# design.net
KiCad netlist of a schematic drawn in Altium Designer
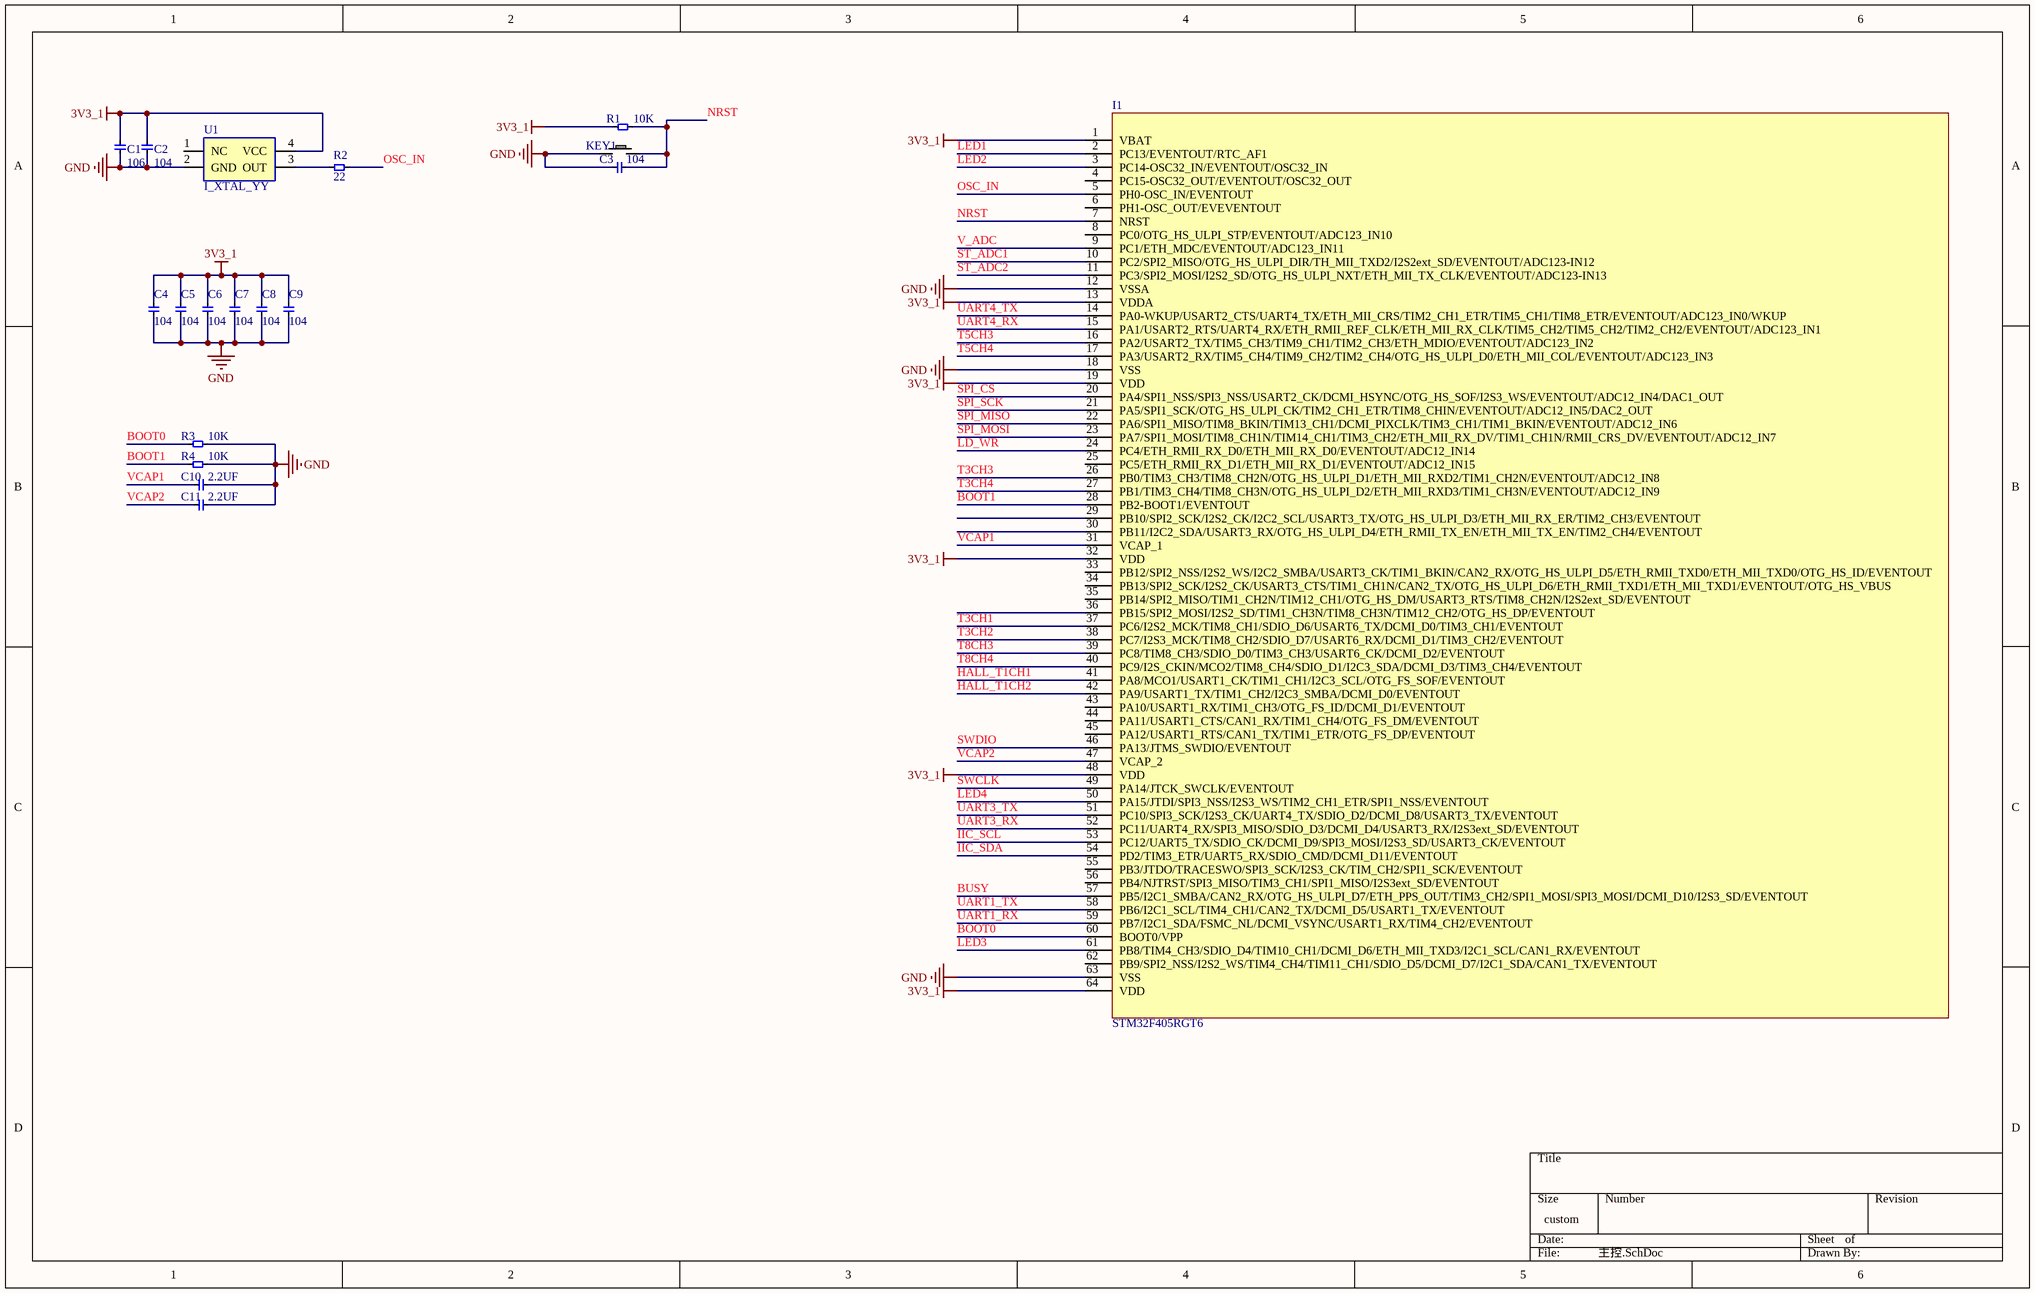
[diagram p0: 主控.SchDoc]

(export (version "E")
  (design (tool "Eeschema 10.0.6"))
  (components
    (comp (ref "C1")
      (value "106")
      (footprint "C_0603")
      (description "无极性贴片电容")
      (libsource (lib "电阻电容电感库") (part "C_无极贴片"))
    )
    (comp (ref "C2")
      (value "104")
      (footprint "C_0603")
      (description "无极性贴片电容")
      (libsource (lib "电阻电容电感库") (part "C_无极贴片"))
    )
    (comp (ref "C3")
      (value "104")
      (footprint "C_0603")
      (description "无极性贴片电容")
      (libsource (lib "电阻电容电感库") (part "C_无极贴片"))
    )
    (comp (ref "C4")
      (value "104")
      (footprint "C_0603")
      (description "无极性贴片电容")
      (libsource (lib "电阻电容电感库") (part "C_无极贴片"))
    )
    (comp (ref "C5")
      (value "104")
      (footprint "C_0603")
      (description "无极性贴片电容")
      (libsource (lib "电阻电容电感库") (part "C_无极贴片"))
    )
    (comp (ref "C6")
      (value "104")
      (footprint "C_0603")
      (description "无极性贴片电容")
      (libsource (lib "电阻电容电感库") (part "C_无极贴片"))
    )
    (comp (ref "C7")
      (value "104")
      (footprint "C_0603")
      (description "无极性贴片电容")
      (libsource (lib "电阻电容电感库") (part "C_无极贴片"))
    )
    (comp (ref "C8")
      (value "104")
      (footprint "C_0603")
      (description "无极性贴片电容")
      (libsource (lib "电阻电容电感库") (part "C_无极贴片"))
    )
    (comp (ref "C9")
      (value "104")
      (footprint "C_0603")
      (description "无极性贴片电容")
      (libsource (lib "电阻电容电感库") (part "C_无极贴片"))
    )
    (comp (ref "C10")
      (value "2.2UF")
      (footprint "C_0603")
      (description "无极性贴片电容")
      (libsource (lib "电阻电容电感库") (part "C_无极贴片"))
    )
    (comp (ref "C11")
      (value "2.2UF")
      (footprint "C_0603")
      (description "无极性贴片电容")
      (libsource (lib "电阻电容电感库") (part "C_无极贴片"))
    )
    (comp (ref "I1")
      (value "STM32F405RGT6")
      (footprint "I_LQFP-64")
      (description "LQFP-64")
      (libsource (lib "集成器件") (part "I_STM32F405RGT6"))
    )
    (comp (ref "KEY1") (value "KEY") (footprint "按键_小四脚") (libsource (lib "王建勇") (part "按键")))
    (comp (ref "R1")
      (value "10K")
      (footprint "R_0603")
      (description "贴片电阻")
      (libsource (lib "电阻电容电感库") (part "R_贴片"))
    )
    (comp (ref "R2")
      (value "22")
      (footprint "R_0603")
      (description "贴片电阻")
      (libsource (lib "电阻电容电感库") (part "R_贴片"))
    )
    (comp (ref "R3")
      (value "10K")
      (footprint "R_0603")
      (description "贴片电阻")
      (libsource (lib "电阻电容电感库") (part "R_贴片"))
    )
    (comp (ref "R4")
      (value "10K")
      (footprint "R_0603")
      (description "贴片电阻")
      (libsource (lib "电阻电容电感库") (part "R_贴片"))
    )
    (comp (ref "U1")
      (value "I_XTAL_YY")
      (footprint "I_XTAL_YYSMD_3.2X2.5")
      (description "有源晶振")
      (libsource (lib "集成器件") (part "I_XTAL_YY"))
    )
  )
  (nets
    (net (code "1") (name "/BOOT0") (class "Default")
      (node (ref "I1") (pin "60") (pinfunction "BOOT0/VPP_60") (pintype "power_in"))
      (node (ref "R3") (pin "1") (pintype "passive"))
    )
    (net (code "2") (name "/BOOT1") (class "Default")
      (node (ref "I1") (pin "28") (pinfunction "PB2-BOOT1/EVENTOUT_28") (pintype "power_in"))
      (node (ref "R4") (pin "1") (pintype "passive"))
    )
    (net (code "3") (name "/BUSY") (class "Default")
      (node (ref "I1") (pin "57") (pinfunction "PB5/I2C1_SMBA/CAN2_RX/OTG_HS_ULPI_D7/ETH_PPS_OUT/TIM3_CH2/SPI1_MOSI/SPI3_MOSI/DCMI_D10/I2S3_SD/EVENTOUT_57") (pintype "power_in"))
    )
    (net (code "4") (name "/HALL_T1CH1") (class "Default")
      (node (ref "I1") (pin "41") (pinfunction "PA8/MCO1/USART1_CK/TIM1_CH1/I2C3_SCL/OTG_FS_SOF/EVENTOUT_41") (pintype "power_in"))
    )
    (net (code "5") (name "/HALL_T1CH2") (class "Default")
      (node (ref "I1") (pin "42") (pinfunction "PA9/USART1_TX/TIM1_CH2/I2C3_SMBA/DCMI_D0/EVENTOUT_42") (pintype "power_in"))
    )
    (net (code "6") (name "/IIC_SCL") (class "Default")
      (node (ref "I1") (pin "53") (pinfunction "PC12/UART5_TX/SDIO_CK/DCMI_D9/SPI3_MOSI/I2S3_SD/USART3_CK/EVENTOUT_53") (pintype "power_in"))
    )
    (net (code "7") (name "/IIC_SDA") (class "Default")
      (node (ref "I1") (pin "54") (pinfunction "PD2/TIM3_ETR/UART5_RX/SDIO_CMD/DCMI_D11/EVENTOUT_54") (pintype "power_in"))
    )
    (net (code "8") (name "/LD_WR") (class "Default")
      (node (ref "I1") (pin "24") (pinfunction "PC4/ETH_RMII_RX_D0/ETH_MII_RX_D0/EVENTOUT/ADC12_IN14_24") (pintype "power_in"))
    )
    (net (code "9") (name "/LED1") (class "Default")
      (node (ref "I1") (pin "2") (pinfunction "PC13/EVENTOUT/RTC_AF1_2") (pintype "power_in"))
    )
    (net (code "10") (name "/LED2") (class "Default")
      (node (ref "I1") (pin "3") (pinfunction "PC14-OSC32_IN/EVENTOUT/OSC32_IN_3") (pintype "power_in"))
    )
    (net (code "11") (name "/LED3") (class "Default")
      (node (ref "I1") (pin "61") (pinfunction "PB8/TIM4_CH3/SDIO_D4/TIM10_CH1/DCMI_D6/ETH_MII_TXD3/I2C1_SCL/CAN1_RX/EVENTOUT_61") (pintype "power_in"))
    )
    (net (code "12") (name "/LED4") (class "Default")
      (node (ref "I1") (pin "50") (pinfunction "PA15/JTDI/SPI3_NSS/I2S3_WS/TIM2_CH1_ETR/SPI1_NSS/EVENTOUT_50") (pintype "power_in"))
    )
    (net (code "13") (name "/NRST") (class "Default")
      (node (ref "C3") (pin "1") (pinfunction "1_1") (pintype "passive"))
      (node (ref "I1") (pin "7") (pinfunction "NRST_7") (pintype "power_in"))
      (node (ref "KEY1") (pin "2") (pinfunction "1_2") (pintype "passive"))
      (node (ref "R1") (pin "2") (pintype "passive"))
    )
    (net (code "14") (name "/OSC_IN") (class "Default")
      (node (ref "I1") (pin "5") (pinfunction "PH0-OSC_IN/EVENTOUT_5") (pintype "power_in"))
      (node (ref "R2") (pin "2") (pintype "passive"))
    )
    (net (code "15") (name "/SPI_CS") (class "Default")
      (node (ref "I1") (pin "20") (pinfunction "PA4/SPI1_NSS/SPI3_NSS/USART2_CK/DCMI_HSYNC/OTG_HS_SOF/I2S3_WS/EVENTOUT/ADC12_IN4/DAC1_OUT_20") (pintype "power_in"))
    )
    (net (code "16") (name "/SPI_MISO") (class "Default")
      (node (ref "I1") (pin "22") (pinfunction "PA6/SPI1_MISO/TIM8_BKIN/TIM13_CH1/DCMI_PIXCLK/TIM3_CH1/TIM1_BKIN/EVENTOUT/ADC12_IN6_22") (pintype "power_in"))
    )
    (net (code "17") (name "/SPI_MOSI") (class "Default")
      (node (ref "I1") (pin "23") (pinfunction "PA7/SPI1_MOSI/TIM8_CH1N/TIM14_CH1/TIM3_CH2/ETH_MII_RX_DV/TIM1_CH1N/RMII_CRS_DV/EVENTOUT/ADC12_IN7_23") (pintype "power_in"))
    )
    (net (code "18") (name "/SPI_SCK") (class "Default")
      (node (ref "I1") (pin "21") (pinfunction "PA5/SPI1_SCK/OTG_HS_ULPI_CK/TIM2_CH1_ETR/TIM8_CHIN/EVENTOUT/ADC12_IN5/DAC2_OUT_21") (pintype "power_in"))
    )
    (net (code "19") (name "/ST_ADC1") (class "Default")
      (node (ref "I1") (pin "10") (pinfunction "PC2/SPI2_MISO/OTG_HS_ULPI_DIR/TH_MII_TXD2/I2S2ext_SD/EVENTOUT/ADC123-IN12_10") (pintype "power_in"))
    )
    (net (code "20") (name "/ST_ADC2") (class "Default")
      (node (ref "I1") (pin "11") (pinfunction "PC3/SPI2_MOSI/I2S2_SD/OTG_HS_ULPI_NXT/ETH_MII_TX_CLK/EVENTOUT/ADC123-IN13_11") (pintype "power_in"))
    )
    (net (code "21") (name "/SWCLK") (class "Default")
      (node (ref "I1") (pin "49") (pinfunction "PA14/JTCK_SWCLK/EVENTOUT_49") (pintype "power_in"))
    )
    (net (code "22") (name "/SWDIO") (class "Default")
      (node (ref "I1") (pin "46") (pinfunction "PA13/JTMS_SWDIO/EVENTOUT_46") (pintype "power_in"))
    )
    (net (code "23") (name "/T3CH1") (class "Default")
      (node (ref "I1") (pin "37") (pinfunction "PC6/I2S2_MCK/TIM8_CH1/SDIO_D6/USART6_TX/DCMI_D0/TIM3_CH1/EVENTOUT_37") (pintype "power_in"))
    )
    (net (code "24") (name "/T3CH2") (class "Default")
      (node (ref "I1") (pin "38") (pinfunction "PC7/I2S3_MCK/TIM8_CH2/SDIO_D7/USART6_RX/DCMI_D1/TIM3_CH2/EVENTOUT_38") (pintype "power_in"))
    )
    (net (code "25") (name "/T3CH3") (class "Default")
      (node (ref "I1") (pin "26") (pinfunction "PB0/TIM3_CH3/TIM8_CH2N/OTG_HS_ULPI_D1/ETH_MII_RXD2/TIM1_CH2N/EVENTOUT/ADC12_IN8_26") (pintype "power_in"))
    )
    (net (code "26") (name "/T3CH4") (class "Default")
      (node (ref "I1") (pin "27") (pinfunction "PB1/TIM3_CH4/TIM8_CH3N/OTG_HS_ULPI_D2/ETH_MII_RXD3/TIM1_CH3N/EVENTOUT/ADC12_IN9_27") (pintype "power_in"))
    )
    (net (code "27") (name "/T5CH3") (class "Default")
      (node (ref "I1") (pin "16") (pinfunction "PA2/USART2_TX/TIM5_CH3/TIM9_CH1/TIM2_CH3/ETH_MDIO/EVENTOUT/ADC123_IN2_16") (pintype "power_in"))
    )
    (net (code "28") (name "/T5CH4") (class "Default")
      (node (ref "I1") (pin "17") (pinfunction "PA3/USART2_RX/TIM5_CH4/TIM9_CH2/TIM2_CH4/OTG_HS_ULPI_D0/ETH_MII_COL/EVENTOUT/ADC123_IN3_17") (pintype "power_in"))
    )
    (net (code "29") (name "/T8CH3") (class "Default")
      (node (ref "I1") (pin "39") (pinfunction "PC8/TIM8_CH3/SDIO_D0/TIM3_CH3/USART6_CK/DCMI_D2/EVENTOUT_39") (pintype "power_in"))
    )
    (net (code "30") (name "/T8CH4") (class "Default")
      (node (ref "I1") (pin "40") (pinfunction "PC9/I2S_CKIN/MCO2/TIM8_CH4/SDIO_D1/I2C3_SDA/DCMI_D3/TIM3_CH4/EVENTOUT_40") (pintype "power_in"))
    )
    (net (code "31") (name "/UART1_RX") (class "Default")
      (node (ref "I1") (pin "59") (pinfunction "PB7/I2C1_SDA/FSMC_NL/DCMI_VSYNC/USART1_RX/TIM4_CH2/EVENTOUT_59") (pintype "power_in"))
    )
    (net (code "32") (name "/UART1_TX") (class "Default")
      (node (ref "I1") (pin "58") (pinfunction "PB6/I2C1_SCL/TIM4_CH1/CAN2_TX/DCMI_D5/USART1_TX/EVENTOUT_58") (pintype "power_in"))
    )
    (net (code "33") (name "/UART3_RX") (class "Default")
      (node (ref "I1") (pin "52") (pinfunction "PC11/UART4_RX/SPI3_MISO/SDIO_D3/DCMI_D4/USART3_RX/I2S3ext_SD/EVENTOUT_52") (pintype "power_in"))
    )
    (net (code "34") (name "/UART3_TX") (class "Default")
      (node (ref "I1") (pin "51") (pinfunction "PC10/SPI3_SCK/I2S3_CK/UART4_TX/SDIO_D2/DCMI_D8/USART3_TX/EVENTOUT_51") (pintype "power_in"))
    )
    (net (code "35") (name "/UART4_RX") (class "Default")
      (node (ref "I1") (pin "15") (pinfunction "PA1/USART2_RTS/UART4_RX/ETH_RMII_REF_CLK/ETH_MII_RX_CLK/TIM5_CH2/TIM5_CH2/TIM2_CH2/EVENTOUT/ADC123_IN1_15") (pintype "power_in"))
    )
    (net (code "36") (name "/UART4_TX") (class "Default")
      (node (ref "I1") (pin "14") (pinfunction "PA0-WKUP/USART2_CTS/UART4_TX/ETH_MII_CRS/TIM2_CH1_ETR/TIM5_CH1/TIM8_ETR/EVENTOUT/ADC123_IN0/WKUP_14") (pintype "power_in"))
    )
    (net (code "37") (name "/VCAP1") (class "Default")
      (node (ref "C10") (pin "2") (pinfunction "2_2") (pintype "passive"))
      (node (ref "I1") (pin "31") (pinfunction "VCAP_1_31") (pintype "power_in"))
    )
    (net (code "38") (name "/VCAP2") (class "Default")
      (node (ref "C11") (pin "2") (pinfunction "2_2") (pintype "passive"))
      (node (ref "I1") (pin "47") (pinfunction "VCAP_2_47") (pintype "power_in"))
    )
    (net (code "39") (name "/V_ADC") (class "Default")
      (node (ref "I1") (pin "9") (pinfunction "PC1/ETH_MDC/EVENTOUT/ADC123_IN11_9") (pintype "power_in"))
    )
    (net (code "40") (name "3V3_1") (class "Default")
      (node (ref "C1") (pin "2") (pinfunction "2_2") (pintype "passive"))
      (node (ref "C2") (pin "2") (pinfunction "2_2") (pintype "passive"))
      (node (ref "C4") (pin "2") (pinfunction "2_2") (pintype "passive"))
      (node (ref "C5") (pin "2") (pinfunction "2_2") (pintype "passive"))
      (node (ref "C6") (pin "2") (pinfunction "2_2") (pintype "passive"))
      (node (ref "C7") (pin "2") (pinfunction "2_2") (pintype "passive"))
      (node (ref "C8") (pin "2") (pinfunction "2_2") (pintype "passive"))
      (node (ref "C9") (pin "2") (pinfunction "2_2") (pintype "passive"))
      (node (ref "I1") (pin "1") (pinfunction "VBAT_1") (pintype "power_in"))
      (node (ref "I1") (pin "13") (pinfunction "VDDA_13") (pintype "power_in"))
      (node (ref "I1") (pin "19") (pinfunction "VDD_19") (pintype "power_in"))
      (node (ref "I1") (pin "32") (pinfunction "VDD_32") (pintype "power_in"))
      (node (ref "I1") (pin "48") (pinfunction "VDD_48") (pintype "power_in"))
      (node (ref "I1") (pin "64") (pinfunction "VDD_64") (pintype "power_in"))
      (node (ref "R1") (pin "1") (pintype "passive"))
      (node (ref "U1") (pin "4") (pinfunction "VCC_4") (pintype "passive"))
    )
    (net (code "41") (name "GND") (class "Default")
      (node (ref "C1") (pin "1") (pinfunction "1_1") (pintype "passive"))
      (node (ref "C10") (pin "1") (pinfunction "1_1") (pintype "passive"))
      (node (ref "C11") (pin "1") (pinfunction "1_1") (pintype "passive"))
      (node (ref "C2") (pin "1") (pinfunction "1_1") (pintype "passive"))
      (node (ref "C3") (pin "2") (pinfunction "2_2") (pintype "passive"))
      (node (ref "C4") (pin "1") (pinfunction "1_1") (pintype "passive"))
      (node (ref "C5") (pin "1") (pinfunction "1_1") (pintype "passive"))
      (node (ref "C6") (pin "1") (pinfunction "1_1") (pintype "passive"))
      (node (ref "C7") (pin "1") (pinfunction "1_1") (pintype "passive"))
      (node (ref "C8") (pin "1") (pinfunction "1_1") (pintype "passive"))
      (node (ref "C9") (pin "1") (pinfunction "1_1") (pintype "passive"))
      (node (ref "I1") (pin "12") (pinfunction "VSSA_12") (pintype "power_in"))
      (node (ref "I1") (pin "18") (pinfunction "VSS_18") (pintype "power_in"))
      (node (ref "I1") (pin "63") (pinfunction "VSS_63") (pintype "power_in"))
      (node (ref "KEY1") (pin "1") (pinfunction "0_1") (pintype "passive"))
      (node (ref "R3") (pin "2") (pintype "passive"))
      (node (ref "R4") (pin "2") (pintype "passive"))
      (node (ref "U1") (pin "2") (pinfunction "GND_2") (pintype "passive"))
    )
    (net (code "42") (name "Net-(U1-OUT)") (class "Default")
      (node (ref "R2") (pin "1") (pintype "passive"))
      (node (ref "U1") (pin "3") (pinfunction "OUT_3") (pintype "passive"))
    )
    (net (code "43") (name "unconnected-(I1-PA10{slash}USART1_RX{slash}TIM1_CH3{slash}OTG_FS_ID{slash}DCMI_D1{slash}EVENTOUT-Pad43)") (class "Default")
      (node (ref "I1") (pin "43") (pinfunction "PA10/USART1_RX/TIM1_CH3/OTG_FS_ID/DCMI_D1/EVENTOUT_43") (pintype "power_in"))
    )
    (net (code "44") (name "unconnected-(I1-PA11{slash}USART1_CTS{slash}CAN1_RX{slash}TIM1_CH4{slash}OTG_FS_DM{slash}EVENTOUT-Pad44)") (class "Default")
      (node (ref "I1") (pin "44") (pinfunction "PA11/USART1_CTS/CAN1_RX/TIM1_CH4/OTG_FS_DM/EVENTOUT_44") (pintype "power_in"))
    )
    (net (code "45") (name "unconnected-(I1-PA12{slash}USART1_RTS{slash}CAN1_TX{slash}TIM1_ETR{slash}OTG_FS_DP{slash}EVENTOUT-Pad45)") (class "Default")
      (node (ref "I1") (pin "45") (pinfunction "PA12/USART1_RTS/CAN1_TX/TIM1_ETR/OTG_FS_DP/EVENTOUT_45") (pintype "power_in"))
    )
    (net (code "46") (name "unconnected-(I1-PB3{slash}JTDO{slash}TRACESWO{slash}SPI3_SCK{slash}I2S3_CK{slash}TIM_CH2{slash}SPI1_SCK{slash}EVENTOUT-Pad55)") (class "Default")
      (node (ref "I1") (pin "55") (pinfunction "PB3/JTDO/TRACESWO/SPI3_SCK/I2S3_CK/TIM_CH2/SPI1_SCK/EVENTOUT_55") (pintype "power_in"))
    )
    (net (code "47") (name "unconnected-(I1-PB4{slash}NJTRST{slash}SPI3_MISO{slash}TIM3_CH1{slash}SPI1_MISO{slash}I2S3ext_SD{slash}EVENTOUT-Pad56)") (class "Default")
      (node (ref "I1") (pin "56") (pinfunction "PB4/NJTRST/SPI3_MISO/TIM3_CH1/SPI1_MISO/I2S3ext_SD/EVENTOUT_56") (pintype "power_in"))
    )
    (net (code "48") (name "unconnected-(I1-PB9{slash}SPI2_NSS{slash}I2S2_WS{slash}TIM4_CH4{slash}TIM11_CH1{slash}SDIO_D5{slash}DCMI_D7{slash}I2C1_SDA{slash}CAN1_TX{slash}EVENTOUT-Pad62)") (class "Default")
      (node (ref "I1") (pin "62") (pinfunction "PB9/SPI2_NSS/I2S2_WS/TIM4_CH4/TIM11_CH1/SDIO_D5/DCMI_D7/I2C1_SDA/CAN1_TX/EVENTOUT_62") (pintype "power_in"))
    )
    (net (code "49") (name "unconnected-(I1-PB10{slash}SPI2_SCK{slash}I2S2_CK{slash}I2C2_SCL{slash}USART3_TX{slash}OTG_HS_ULPI_D3{slash}ETH_MII_RX_ER{slash}TIM2_CH3{slash}EVENTOUT-Pad29)") (class "Default")
      (node (ref "I1") (pin "29") (pinfunction "PB10/SPI2_SCK/I2S2_CK/I2C2_SCL/USART3_TX/OTG_HS_ULPI_D3/ETH_MII_RX_ER/TIM2_CH3/EVENTOUT_29") (pintype "power_in"))
    )
    (net (code "50") (name "unconnected-(I1-PB11{slash}I2C2_SDA{slash}USART3_RX{slash}OTG_HS_ULPI_D4{slash}ETH_RMII_TX_EN{slash}ETH_MII_TX_EN{slash}TIM2_CH4{slash}EVENTOUT-Pad30)") (class "Default")
      (node (ref "I1") (pin "30") (pinfunction "PB11/I2C2_SDA/USART3_RX/OTG_HS_ULPI_D4/ETH_RMII_TX_EN/ETH_MII_TX_EN/TIM2_CH4/EVENTOUT_30") (pintype "power_in"))
    )
    (net (code "51") (name "unconnected-(I1-PB12{slash}SPI2_NSS{slash}I2S2_WS{slash}I2C2_SMBA{slash}USART3_CK{slash}TIM1_BKIN{slash}CAN2_RX{slash}OTG_HS_ULPI_D5{slash}ETH_RMII_TXD0{slash}ETH_MII_TXD0{slash}OTG_HS_ID{slash}EVENTOUT-Pad33)") (class "Default")
      (node (ref "I1") (pin "33") (pinfunction "PB12/SPI2_NSS/I2S2_WS/I2C2_SMBA/USART3_CK/TIM1_BKIN/CAN2_RX/OTG_HS_ULPI_D5/ETH_RMII_TXD0/ETH_MII_TXD0/OTG_HS_ID/EVENTOUT_33") (pintype "power_in"))
    )
    (net (code "52") (name "unconnected-(I1-PB13{slash}SPI2_SCK{slash}I2S2_CK{slash}USART3_CTS{slash}TIM1_CH1N{slash}CAN2_TX{slash}OTG_HS_ULPI_D6{slash}ETH_RMII_TXD1{slash}ETH_MII_TXD1{slash}EVENTOUT{slash}OTG_HS_VBUS-Pad34)") (class "Default")
      (node (ref "I1") (pin "34") (pinfunction "PB13/SPI2_SCK/I2S2_CK/USART3_CTS/TIM1_CH1N/CAN2_TX/OTG_HS_ULPI_D6/ETH_RMII_TXD1/ETH_MII_TXD1/EVENTOUT/OTG_HS_VBUS_34") (pintype "power_in"))
    )
    (net (code "53") (name "unconnected-(I1-PB14{slash}SPI2_MISO{slash}TIM1_CH2N{slash}TIM12_CH1{slash}OTG_HS_DM{slash}USART3_RTS{slash}TIM8_CH2N{slash}I2S2ext_SD{slash}EVENTOUT-Pad35)") (class "Default")
      (node (ref "I1") (pin "35") (pinfunction "PB14/SPI2_MISO/TIM1_CH2N/TIM12_CH1/OTG_HS_DM/USART3_RTS/TIM8_CH2N/I2S2ext_SD/EVENTOUT_35") (pintype "power_in"))
    )
    (net (code "54") (name "unconnected-(I1-PB15{slash}SPI2_MOSI{slash}I2S2_SD{slash}TIM1_CH3N{slash}TIM8_CH3N{slash}TIM12_CH2{slash}OTG_HS_DP{slash}EVENTOUT-Pad36)") (class "Default")
      (node (ref "I1") (pin "36") (pinfunction "PB15/SPI2_MOSI/I2S2_SD/TIM1_CH3N/TIM8_CH3N/TIM12_CH2/OTG_HS_DP/EVENTOUT_36") (pintype "power_in"))
    )
    (net (code "55") (name "unconnected-(I1-PC0{slash}OTG_HS_ULPI_STP{slash}EVENTOUT{slash}ADC123_IN10-Pad8)") (class "Default")
      (node (ref "I1") (pin "8") (pinfunction "PC0/OTG_HS_ULPI_STP/EVENTOUT/ADC123_IN10_8") (pintype "power_in"))
    )
    (net (code "56") (name "unconnected-(I1-PC5{slash}ETH_RMII_RX_D1{slash}ETH_MII_RX_D1{slash}EVENTOUT{slash}ADC12_IN15-Pad25)") (class "Default")
      (node (ref "I1") (pin "25") (pinfunction "PC5/ETH_RMII_RX_D1/ETH_MII_RX_D1/EVENTOUT/ADC12_IN15_25") (pintype "power_in"))
    )
    (net (code "57") (name "unconnected-(I1-PC15-OSC32_OUT{slash}EVENTOUT{slash}OSC32_OUT-Pad4)") (class "Default")
      (node (ref "I1") (pin "4") (pinfunction "PC15-OSC32_OUT/EVENTOUT/OSC32_OUT_4") (pintype "power_in"))
    )
    (net (code "58") (name "unconnected-(I1-PH1-OSC_OUT{slash}EVEVENTOUT-Pad6)") (class "Default")
      (node (ref "I1") (pin "6") (pinfunction "PH1-OSC_OUT/EVEVENTOUT_6") (pintype "power_in"))
    )
    (net (code "59") (name "unconnected-(U1-NC-Pad1)") (class "Default")
      (node (ref "U1") (pin "1") (pinfunction "NC_1") (pintype "passive"))
    )
  )
)
